# 08_power.net
KiCad netlist of a schematic drawn in Altium Designer
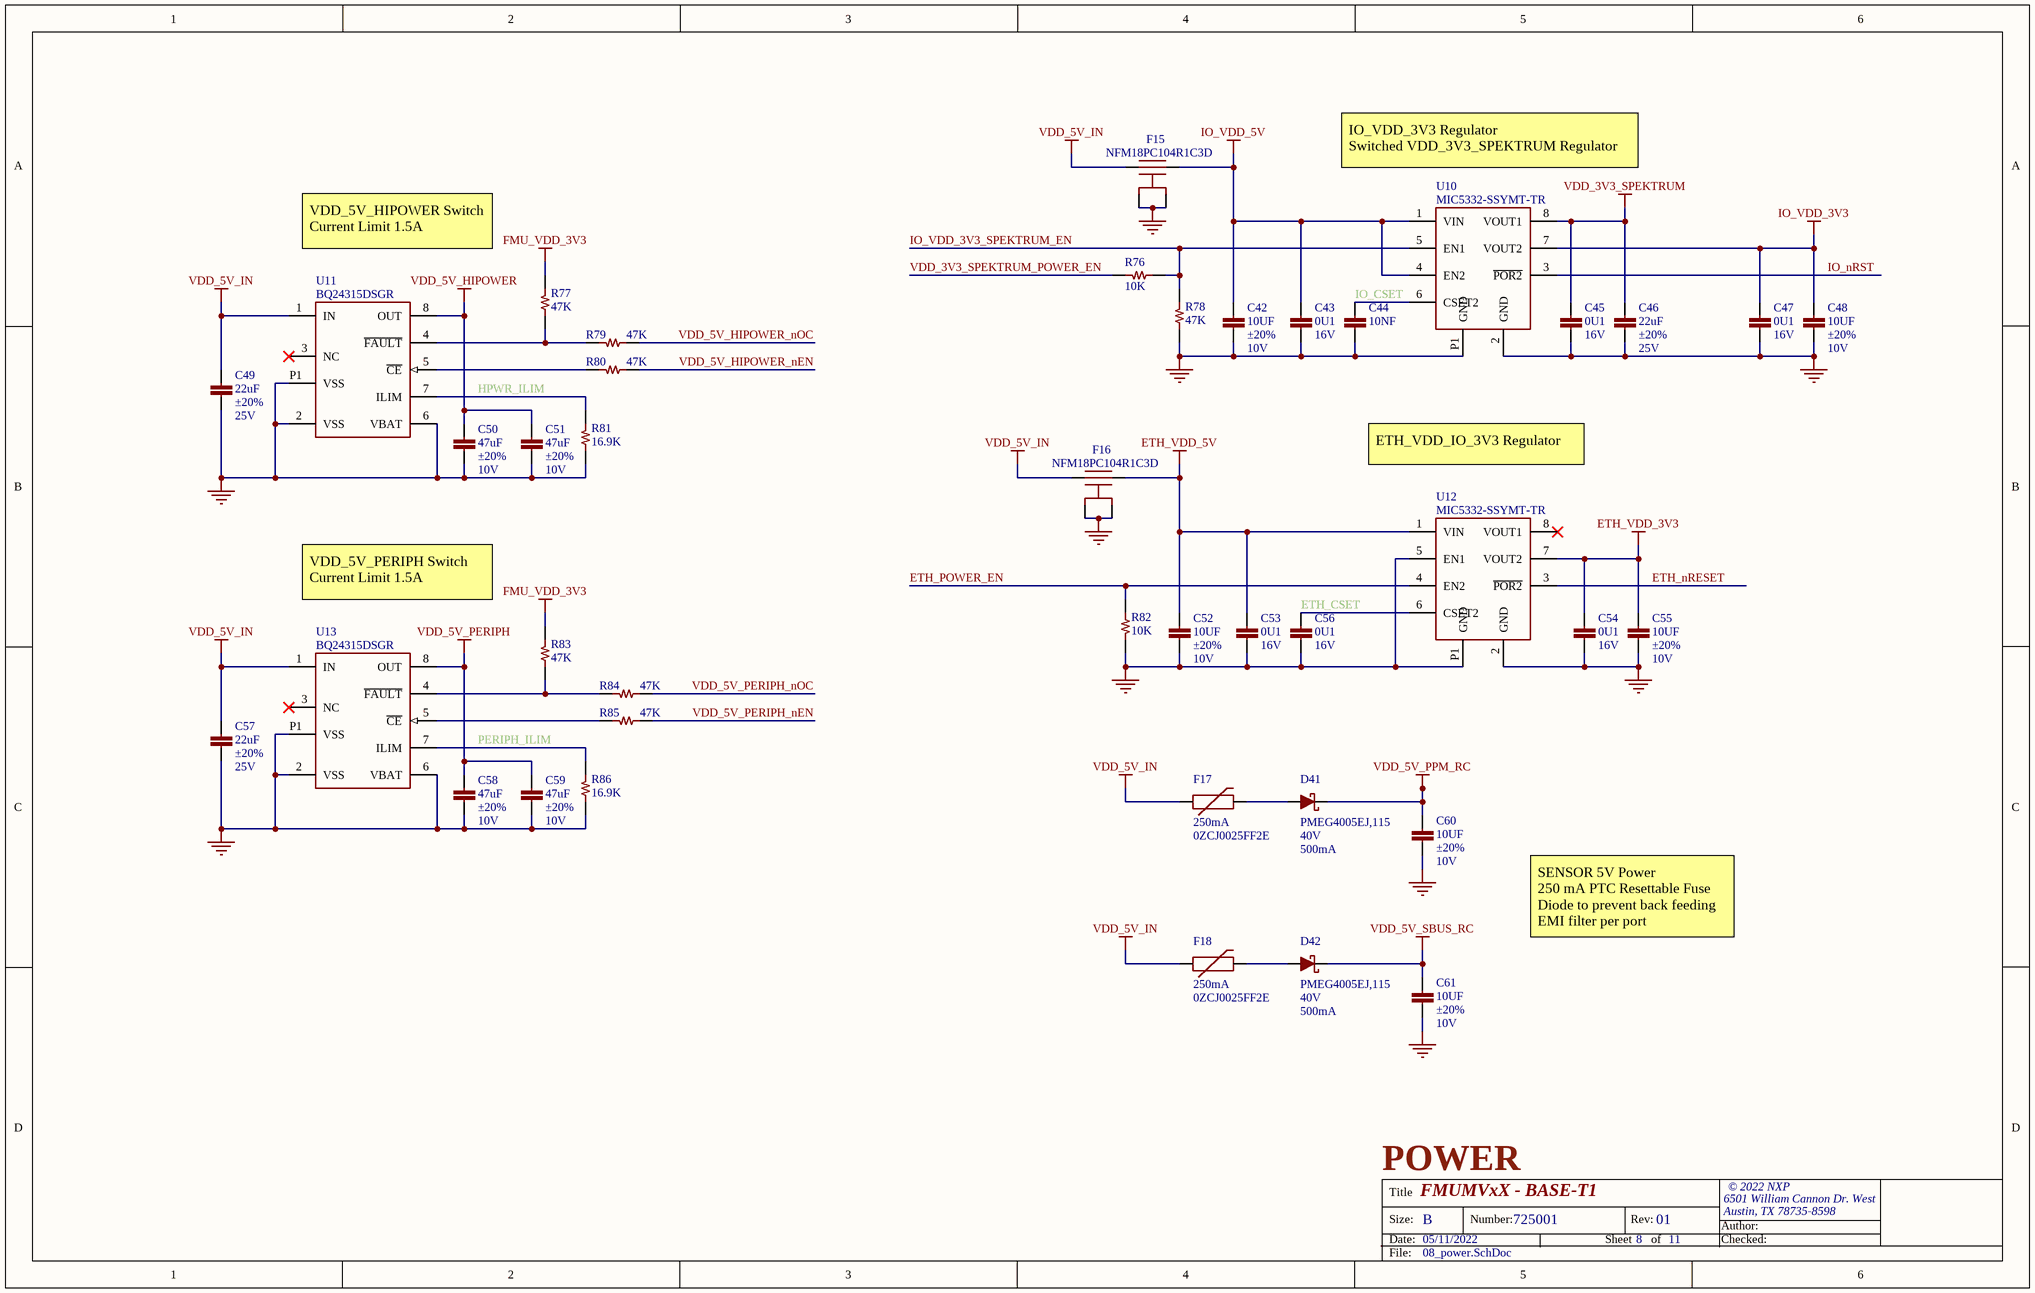
[diagram p0: 08_power.SchDoc]

(export (version "E")
  (design (tool "Eeschema 10.0.6"))
  (components
    (comp (ref "C42")
      (value "10UF")
      (footprint "CAPC100X50X56L25N")
      (description "CAP CER 10UF 20% 10V X5R 0402")
      (fields
        (field (name "MANUFACTURER") "Samsung Electro-Mechanics")
        (field (name "MANUFACTURER PART NUMBER") "CL05A106MP5NUNC")
        (field (name "TOLERANCE") "±20%")
        (field (name "VOLTAGE - RATED") "10V")
      )
      (libsource (lib "NscDG_Integrated_Library") (part "CAP_10UF_20%_10V_X5R_0402"))
    )
    (comp (ref "C43")
      (value "0U1")
      (footprint "CAPC100X50X56L25N")
      (description "CAP CER 0.1UF 10% 16V X7R 0402")
      (fields
        (field (name "TOLERANCE") "±10%")
        (field (name "MANUFACTURER") "Murata Electronics")
        (field (name "VOLTAGE - RATED") "16V")
      )
      (libsource (lib "NscDG_Integrated_Library") (part "CAP_0U1_16V_X7R_0402"))
    )
    (comp (ref "C44")
      (value "10NF")
      (footprint "CAPC100X50X56L25N")
      (description "CAP CER 10NF 10% 50V X7R 0402")
      (fields
        (field (name "TOLERANCE") "±10%")
        (field (name "MANUFACTURER") "Murata Electronics North America")
      )
      (libsource (lib "NscDG_Integrated_Library") (part "CAP_10NF_10%_50V_X7R_0402"))
    )
    (comp (ref "C45")
      (value "0U1")
      (footprint "CAPC100X50X56L25N")
      (description "CAP CER 0.1UF 10% 16V X7R 0402")
      (fields
        (field (name "TOLERANCE") "±10%")
        (field (name "MANUFACTURER") "Murata Electronics")
        (field (name "VOLTAGE - RATED") "16V")
      )
      (libsource (lib "NscDG_Integrated_Library") (part "CAP_0U1_16V_X7R_0402"))
    )
    (comp (ref "C46")
      (value "22uF")
      (footprint "CAPC200X125X70L40N")
      (description "CAP CER 22UF 20% 25V X5R 0805")
      (fields
        (field (name "MANUFACTURER") "Murata Electronics")
        (field (name "MANUFACTURER PART NUMBER") "GRT21BR61E226ME13L")
        (field (name "TOLERANCE") "±20%")
        (field (name "VOLTAGE - RATED") "25V")
      )
      (libsource (lib "NscDG_Integrated_Library") (part "CAP_22UF_20%_25V_X5R_0805"))
    )
    (comp (ref "C47")
      (value "0U1")
      (footprint "CAPC100X50X56L25N")
      (description "CAP CER 0.1UF 10% 16V X7R 0402")
      (fields
        (field (name "TOLERANCE") "±10%")
        (field (name "MANUFACTURER") "Murata Electronics")
        (field (name "VOLTAGE - RATED") "16V")
      )
      (libsource (lib "NscDG_Integrated_Library") (part "CAP_0U1_16V_X7R_0402"))
    )
    (comp (ref "C48")
      (value "10UF")
      (footprint "CAPC100X50X56L25N")
      (description "CAP CER 10UF 20% 10V X5R 0402")
      (fields
        (field (name "MANUFACTURER") "Samsung Electro-Mechanics")
        (field (name "MANUFACTURER PART NUMBER") "CL05A106MP5NUNC")
        (field (name "TOLERANCE") "±20%")
        (field (name "VOLTAGE - RATED") "10V")
      )
      (libsource (lib "NscDG_Integrated_Library") (part "CAP_10UF_20%_10V_X5R_0402"))
    )
    (comp (ref "C49")
      (value "22uF")
      (footprint "CAPC200X125X70L40N")
      (description "CAP CER 22UF 20% 25V X5R 0805")
      (fields
        (field (name "MANUFACTURER") "Murata Electronics")
        (field (name "MANUFACTURER PART NUMBER") "GRT21BR61E226ME13L")
        (field (name "TOLERANCE") "±20%")
        (field (name "VOLTAGE - RATED") "25V")
      )
      (libsource (lib "NscDG_Integrated_Library") (part "CAP_22UF_20%_25V_X5R_0805"))
    )
    (comp (ref "C50")
      (value "47uF")
      (footprint "CAPC200X125X145L45N")
      (description "CAP CER 47UF 20% 10V X5R 0805")
      (fields
        (field (name "MANUFACTURER") "Murata Electronics North America")
        (field (name "MANUFACTURER PART NUMBER") "GRM21BR61A476ME15L")
        (field (name "TOLERANCE") "±20%")
        (field (name "VOLTAGE - RATED") "10V")
      )
      (libsource (lib "NscDG_Integrated_Library") (part "CAP_47UF_20%_10V_X5R_0805"))
    )
    (comp (ref "C51")
      (value "47uF")
      (footprint "CAPC200X125X145L45N")
      (description "CAP CER 47UF 20% 10V X5R 0805")
      (fields
        (field (name "MANUFACTURER") "Murata Electronics North America")
        (field (name "MANUFACTURER PART NUMBER") "GRM21BR61A476ME15L")
        (field (name "TOLERANCE") "±20%")
        (field (name "VOLTAGE - RATED") "10V")
      )
      (libsource (lib "NscDG_Integrated_Library") (part "CAP_47UF_20%_10V_X5R_0805"))
    )
    (comp (ref "C52")
      (value "10UF")
      (footprint "CAPC100X50X56L25N")
      (description "CAP CER 10UF 20% 10V X5R 0402")
      (fields
        (field (name "MANUFACTURER") "Samsung Electro-Mechanics")
        (field (name "MANUFACTURER PART NUMBER") "CL05A106MP5NUNC")
        (field (name "TOLERANCE") "±20%")
        (field (name "VOLTAGE - RATED") "10V")
      )
      (libsource (lib "NscDG_Integrated_Library") (part "CAP_10UF_20%_10V_X5R_0402"))
    )
    (comp (ref "C53")
      (value "0U1")
      (footprint "CAPC100X50X56L25N")
      (description "CAP CER 0.1UF 10% 16V X7R 0402")
      (fields
        (field (name "TOLERANCE") "±10%")
        (field (name "MANUFACTURER") "Murata Electronics")
        (field (name "VOLTAGE - RATED") "16V")
      )
      (libsource (lib "NscDG_Integrated_Library") (part "CAP_0U1_16V_X7R_0402"))
    )
    (comp (ref "C54")
      (value "0U1")
      (footprint "CAPC100X50X56L25N")
      (description "CAP CER 0.1UF 10% 16V X7R 0402")
      (fields
        (field (name "TOLERANCE") "±10%")
        (field (name "MANUFACTURER") "Murata Electronics")
        (field (name "VOLTAGE - RATED") "16V")
      )
      (libsource (lib "NscDG_Integrated_Library") (part "CAP_0U1_16V_X7R_0402"))
    )
    (comp (ref "C55")
      (value "10UF")
      (footprint "CAPC100X50X56L25N")
      (description "CAP CER 10UF 20% 10V X5R 0402")
      (fields
        (field (name "MANUFACTURER") "Samsung Electro-Mechanics")
        (field (name "MANUFACTURER PART NUMBER") "CL05A106MP5NUNC")
        (field (name "TOLERANCE") "±20%")
        (field (name "VOLTAGE - RATED") "10V")
      )
      (libsource (lib "NscDG_Integrated_Library") (part "CAP_10UF_20%_10V_X5R_0402"))
    )
    (comp (ref "C56")
      (value "0U1")
      (footprint "CAPC100X50X56L25N")
      (description "CAP CER 0.1UF 10% 16V X7R 0402")
      (fields
        (field (name "TOLERANCE") "±10%")
        (field (name "MANUFACTURER") "Murata Electronics")
        (field (name "VOLTAGE - RATED") "16V")
      )
      (libsource (lib "NscDG_Integrated_Library") (part "CAP_0U1_16V_X7R_0402"))
    )
    (comp (ref "C57")
      (value "22uF")
      (footprint "CAPC200X125X70L40N")
      (description "CAP CER 22UF 20% 25V X5R 0805")
      (fields
        (field (name "MANUFACTURER") "Murata Electronics")
        (field (name "MANUFACTURER PART NUMBER") "GRT21BR61E226ME13L")
        (field (name "TOLERANCE") "±20%")
        (field (name "VOLTAGE - RATED") "25V")
      )
      (libsource (lib "NscDG_Integrated_Library") (part "CAP_22UF_20%_25V_X5R_0805"))
    )
    (comp (ref "C58")
      (value "47uF")
      (footprint "CAPC200X125X145L45N")
      (description "CAP CER 47UF 20% 10V X5R 0805")
      (fields
        (field (name "MANUFACTURER") "Murata Electronics North America")
        (field (name "MANUFACTURER PART NUMBER") "GRM21BR61A476ME15L")
        (field (name "TOLERANCE") "±20%")
        (field (name "VOLTAGE - RATED") "10V")
      )
      (libsource (lib "NscDG_Integrated_Library") (part "CAP_47UF_20%_10V_X5R_0805"))
    )
    (comp (ref "C59")
      (value "47uF")
      (footprint "CAPC200X125X145L45N")
      (description "CAP CER 47UF 20% 10V X5R 0805")
      (fields
        (field (name "MANUFACTURER") "Murata Electronics North America")
        (field (name "MANUFACTURER PART NUMBER") "GRM21BR61A476ME15L")
        (field (name "TOLERANCE") "±20%")
        (field (name "VOLTAGE - RATED") "10V")
      )
      (libsource (lib "NscDG_Integrated_Library") (part "CAP_47UF_20%_10V_X5R_0805"))
    )
    (comp (ref "C60")
      (value "10UF")
      (footprint "CAPC100X50X56L25N")
      (description "CAP CER 10UF 20% 10V X5R 0402")
      (fields
        (field (name "MANUFACTURER") "Samsung Electro-Mechanics")
        (field (name "MANUFACTURER PART NUMBER") "CL05A106MP5NUNC")
        (field (name "TOLERANCE") "±20%")
        (field (name "VOLTAGE - RATED") "10V")
      )
      (libsource (lib "NscDG_Integrated_Library") (part "CAP_10UF_20%_10V_X5R_0402"))
    )
    (comp (ref "C61")
      (value "10UF")
      (footprint "CAPC100X50X56L25N")
      (description "CAP CER 10UF 20% 10V X5R 0402")
      (fields
        (field (name "MANUFACTURER") "Samsung Electro-Mechanics")
        (field (name "MANUFACTURER PART NUMBER") "CL05A106MP5NUNC")
        (field (name "TOLERANCE") "±20%")
        (field (name "VOLTAGE - RATED") "10V")
      )
      (libsource (lib "NscDG_Integrated_Library") (part "CAP_10UF_20%_10V_X5R_0402"))
    )
    (comp (ref "D41")
      (value "DIODE SCHOTTKY 40V 500MA SOD323F")
      (footprint "SODFL2512X80L40X35N")
      (fields
        (field (name "MANUFACTURER") "Nexperia USA Inc.")
        (field (name "MANUFACTURER PART NUMBER") "PMEG4005EJ,115")
        (field (name "VOLTAGE") "40V")
        (field (name "CURRENT") "500mA")
      )
      (libsource (lib "NscDG_Integrated_Library") (part "DIODE_SCHOTTKY_LOW_VF_40V_500MA_SOD323F"))
    )
    (comp (ref "D42")
      (value "DIODE SCHOTTKY 40V 500MA SOD323F")
      (footprint "SODFL2512X80L40X35N")
      (fields
        (field (name "MANUFACTURER") "Nexperia USA Inc.")
        (field (name "MANUFACTURER PART NUMBER") "PMEG4005EJ,115")
        (field (name "VOLTAGE") "40V")
        (field (name "CURRENT") "500mA")
      )
      (libsource (lib "NscDG_Integrated_Library") (part "DIODE_SCHOTTKY_LOW_VF_40V_500MA_SOD323F"))
    )
    (comp (ref "F15")
      (value "FILTER CAP FEEDTHRU 0.1UF 20% 16V 0603")
      (footprint "NFM18PC104R1C3_0603_NO_VIA")
      (fields
        (field (name "TOLERANCE") "±20%")
        (field (name "MANUFACTURER") "Murata Electronics North America")
        (field (name "MANUFACTURER PART NUMBER") "NFM18PC104R1C3D")
      )
      (libsource (lib "NscDG_Integrated_Library") (part "FILTER_0.1uF_16V_2A_NO_VIA_0603"))
    )
    (comp (ref "F16")
      (value "FILTER CAP FEEDTHRU 0.1UF 20% 16V 0603")
      (footprint "NFM18PC104R1C3_0603_NO_VIA")
      (fields
        (field (name "TOLERANCE") "±20%")
        (field (name "MANUFACTURER") "Murata Electronics North America")
        (field (name "MANUFACTURER PART NUMBER") "NFM18PC104R1C3D")
      )
      (libsource (lib "NscDG_Integrated_Library") (part "FILTER_0.1uF_16V_2A_NO_VIA_0603"))
    )
    (comp (ref "F17")
      (value "FUSE PTC RESETTABLE 250MA 16V 1206")
      (footprint "PTC-1206")
      (fields
        (field (name "MANUFACTURER") "Bel Fuse Inc.")
        (field (name "CURRENT HOLD") "250mA")
        (field (name "MANUFACTURER PART NUMBER") "0ZCJ0025FF2E")
      )
      (libsource (lib "NscDG_Integrated_Library") (part "FUSE_PTC_250MA_SMD"))
    )
    (comp (ref "F18")
      (value "FUSE PTC RESETTABLE 250MA 16V 1206")
      (footprint "PTC-1206")
      (fields
        (field (name "MANUFACTURER") "Bel Fuse Inc.")
        (field (name "CURRENT HOLD") "250mA")
        (field (name "MANUFACTURER PART NUMBER") "0ZCJ0025FF2E")
      )
      (libsource (lib "NscDG_Integrated_Library") (part "FUSE_PTC_250MA_SMD"))
    )
    (comp (ref "R76")
      (value "10K")
      (footprint "RESC100X50X40L25")
      (description "RES SMD 10K OHM 1% 1/16W 0402")
      (fields (field (name "TOLERANCE") "±1%") (field (name "MANUFACTURER") "Vishay Dale"))
      (libsource (lib "NscDG_Integrated_Library") (part "RES_10K_1%_1/16W_0402"))
    )
    (comp (ref "R77")
      (value "47K")
      (footprint "RESC100X50X40L25")
      (description "RES SMD 47K OHM 1% 1/16W 0402")
      (fields (field (name "TOLERANCE") "±1%") (field (name "MANUFACTURER") "Yageo"))
      (libsource (lib "NscDG_Integrated_Library") (part "RES_47K_1%_1/16W_0402"))
    )
    (comp (ref "R78")
      (value "47K")
      (footprint "RESC100X50X40L25")
      (description "RES SMD 47K OHM 1% 1/16W 0402")
      (fields (field (name "TOLERANCE") "±1%") (field (name "MANUFACTURER") "Yageo"))
      (libsource (lib "NscDG_Integrated_Library") (part "RES_47K_1%_1/16W_0402"))
    )
    (comp (ref "R79")
      (value "47K")
      (footprint "RESC100X50X40L25")
      (description "RES SMD 47K OHM 1% 1/16W 0402")
      (fields (field (name "TOLERANCE") "±1%") (field (name "MANUFACTURER") "Yageo"))
      (libsource (lib "NscDG_Integrated_Library") (part "RES_47K_1%_1/16W_0402"))
    )
    (comp (ref "R80")
      (value "47K")
      (footprint "RESC100X50X40L25")
      (description "RES SMD 47K OHM 1% 1/16W 0402")
      (fields (field (name "TOLERANCE") "±1%") (field (name "MANUFACTURER") "Yageo"))
      (libsource (lib "NscDG_Integrated_Library") (part "RES_47K_1%_1/16W_0402"))
    )
    (comp (ref "R81")
      (value "16.9K")
      (footprint "RESC100X50X40L25")
      (description "RES SMD 16.9K OHM 1% 1/16W 0402")
      (fields (field (name "TOLERANCE") "±1%") (field (name "MANUFACTURER") "Yageo"))
      (libsource (lib "NscDG_Integrated_Library") (part "RES_16.9K_1%_1/16W_0402"))
    )
    (comp (ref "R82")
      (value "10K")
      (footprint "RESC100X50X40L25")
      (description "RES SMD 10K OHM 1% 1/16W 0402")
      (fields (field (name "TOLERANCE") "±1%") (field (name "MANUFACTURER") "Vishay Dale"))
      (libsource (lib "NscDG_Integrated_Library") (part "RES_10K_1%_1/16W_0402"))
    )
    (comp (ref "R83")
      (value "47K")
      (footprint "RESC100X50X40L25")
      (description "RES SMD 47K OHM 1% 1/16W 0402")
      (fields (field (name "TOLERANCE") "±1%") (field (name "MANUFACTURER") "Yageo"))
      (libsource (lib "NscDG_Integrated_Library") (part "RES_47K_1%_1/16W_0402"))
    )
    (comp (ref "R84")
      (value "47K")
      (footprint "RESC100X50X40L25")
      (description "RES SMD 47K OHM 1% 1/16W 0402")
      (fields (field (name "TOLERANCE") "±1%") (field (name "MANUFACTURER") "Yageo"))
      (libsource (lib "NscDG_Integrated_Library") (part "RES_47K_1%_1/16W_0402"))
    )
    (comp (ref "R85")
      (value "47K")
      (footprint "RESC100X50X40L25")
      (description "RES SMD 47K OHM 1% 1/16W 0402")
      (fields (field (name "TOLERANCE") "±1%") (field (name "MANUFACTURER") "Yageo"))
      (libsource (lib "NscDG_Integrated_Library") (part "RES_47K_1%_1/16W_0402"))
    )
    (comp (ref "R86")
      (value "16.9K")
      (footprint "RESC100X50X40L25")
      (description "RES SMD 16.9K OHM 1% 1/16W 0402")
      (fields (field (name "TOLERANCE") "±1%") (field (name "MANUFACTURER") "Yageo"))
      (libsource (lib "NscDG_Integrated_Library") (part "RES_16.9K_1%_1/16W_0402"))
    )
    (comp (ref "U10")
      (value "IC REG LIN 3.3V/3.3V 8TMLF")
      (footprint "My_Integrated_Library:SON9P50_200X200X60L35X25T120X60N")
      (fields
        (field (name "MANUFACTURER") "Microchip Technology")
        (field (name "MANUFACTURER PART NUMBER") "MIC5332-SSYMT-TR")
      )
      (libsource (lib "NscDG_Integrated_Library") (part "IC_MIC5332-SSYMT-TR"))
    )
    (comp (ref "U11")
      (value "IC LI+ CHARGER FRONT END 8SON")
      (footprint "SON9P50_200X200X80L30X25T160X80N")
      (fields
        (field (name "MANUFACTURER") "Texas Instruments")
        (field (name "MANUFACTURER PART NUMBER") "BQ24315DSGR")
      )
      (libsource (lib "NscDG_Integrated_Library") (part "IC_BQ24315DSGT_8WSON"))
    )
    (comp (ref "U12")
      (value "IC REG LIN 3.3V/3.3V 8TMLF")
      (footprint "My_Integrated_Library:SON9P50_200X200X60L35X25T120X60N")
      (fields
        (field (name "MANUFACTURER") "Microchip Technology")
        (field (name "MANUFACTURER PART NUMBER") "MIC5332-SSYMT-TR")
      )
      (libsource (lib "NscDG_Integrated_Library") (part "IC_MIC5332-SSYMT-TR"))
    )
    (comp (ref "U13")
      (value "IC LI+ CHARGER FRONT END 8SON")
      (footprint "SON9P50_200X200X80L30X25T160X80N")
      (fields
        (field (name "MANUFACTURER") "Texas Instruments")
        (field (name "MANUFACTURER PART NUMBER") "BQ24315DSGR")
      )
      (libsource (lib "NscDG_Integrated_Library") (part "IC_BQ24315DSGT_8WSON"))
    )
  )
  (nets
    (net (code "1") (name "/ETH_CSET") (class "Default")
      (node (ref "C56") (pin "1") (pinfunction "1_1") (pintype "passive"))
      (node (ref "U12") (pin "6") (pinfunction "CSET2_6") (pintype "passive"))
    )
    (net (code "2") (name "/ETH_POWER_EN") (class "Default")
      (node (ref "R82") (pin "2") (pinfunction "2_2") (pintype "passive"))
      (node (ref "U12") (pin "4") (pinfunction "EN2_4") (pintype "passive"))
    )
    (net (code "3") (name "/ETH_nRESET") (class "Default")
      (node (ref "U12") (pin "3") (pinfunction "~{POR2}_3") (pintype "passive"))
    )
    (net (code "4") (name "/HPWR_ILIM") (class "Default")
      (node (ref "R81") (pin "1") (pinfunction "1_1") (pintype "passive"))
      (node (ref "U11") (pin "7") (pinfunction "ILIM_7") (pintype "passive"))
    )
    (net (code "5") (name "/IO_CSET") (class "Default")
      (node (ref "C44") (pin "1") (pinfunction "1_1") (pintype "passive"))
      (node (ref "U10") (pin "6") (pinfunction "CSET2_6") (pintype "passive"))
    )
    (net (code "6") (name "/IO_VDD_3V3_SPEKTRUM_EN") (class "Default")
      (node (ref "R76") (pin "2") (pinfunction "2_2") (pintype "passive"))
      (node (ref "R78") (pin "1") (pinfunction "1_1") (pintype "passive"))
      (node (ref "U10") (pin "5") (pinfunction "EN1_5") (pintype "passive"))
    )
    (net (code "7") (name "/IO_nRST") (class "Default")
      (node (ref "U10") (pin "3") (pinfunction "~{POR2}_3") (pintype "passive"))
    )
    (net (code "8") (name "/PERIPH_ILIM") (class "Default")
      (node (ref "R86") (pin "1") (pinfunction "1_1") (pintype "passive"))
      (node (ref "U13") (pin "7") (pinfunction "ILIM_7") (pintype "passive"))
    )
    (net (code "9") (name "/VDD_3V3_SPEKTRUM_POWER_EN") (class "Default")
      (node (ref "R76") (pin "1") (pinfunction "1_1") (pintype "passive"))
    )
    (net (code "10") (name "/VDD_5V_HIPOWER_nEN") (class "Default")
      (node (ref "R80") (pin "2") (pinfunction "2_2") (pintype "passive"))
    )
    (net (code "11") (name "/VDD_5V_HIPOWER_nOC") (class "Default")
      (node (ref "R79") (pin "2") (pinfunction "2_2") (pintype "passive"))
    )
    (net (code "12") (name "/VDD_5V_PERIPH_nEN") (class "Default")
      (node (ref "R85") (pin "2") (pinfunction "2_2") (pintype "passive"))
    )
    (net (code "13") (name "/VDD_5V_PERIPH_nOC") (class "Default")
      (node (ref "R84") (pin "2") (pinfunction "2_2") (pintype "passive"))
    )
    (net (code "14") (name "ETH_VDD_3V3") (class "Default")
      (node (ref "C54") (pin "1") (pinfunction "1_1") (pintype "passive"))
      (node (ref "C55") (pin "1") (pinfunction "1_1") (pintype "passive"))
      (node (ref "U12") (pin "7") (pinfunction "VOUT2_7") (pintype "passive"))
    )
    (net (code "15") (name "ETH_VDD_5V") (class "Default")
      (node (ref "C52") (pin "1") (pinfunction "1_1") (pintype "passive"))
      (node (ref "C53") (pin "1") (pinfunction "1_1") (pintype "passive"))
      (node (ref "F16") (pin "3") (pinfunction "3_3") (pintype "passive"))
      (node (ref "U12") (pin "1") (pinfunction "VIN_1") (pintype "power_in"))
    )
    (net (code "16") (name "FMU_VDD_3V3") (class "Default")
      (node (ref "R77") (pin "1") (pinfunction "1_1") (pintype "passive"))
      (node (ref "R83") (pin "1") (pinfunction "1_1") (pintype "passive"))
    )
    (net (code "17") (name "GND") (class "Default")
      (node (ref "C42") (pin "2") (pinfunction "2_2") (pintype "passive"))
      (node (ref "C43") (pin "2") (pinfunction "2_2") (pintype "passive"))
      (node (ref "C44") (pin "2") (pinfunction "2_2") (pintype "passive"))
      (node (ref "C45") (pin "2") (pinfunction "2_2") (pintype "passive"))
      (node (ref "C46") (pin "2") (pinfunction "2_2") (pintype "passive"))
      (node (ref "C47") (pin "2") (pinfunction "2_2") (pintype "passive"))
      (node (ref "C48") (pin "2") (pinfunction "2_2") (pintype "passive"))
      (node (ref "C49") (pin "2") (pinfunction "2_2") (pintype "passive"))
      (node (ref "C50") (pin "2") (pinfunction "2_2") (pintype "passive"))
      (node (ref "C51") (pin "2") (pinfunction "2_2") (pintype "passive"))
      (node (ref "C52") (pin "2") (pinfunction "2_2") (pintype "passive"))
      (node (ref "C53") (pin "2") (pinfunction "2_2") (pintype "passive"))
      (node (ref "C54") (pin "2") (pinfunction "2_2") (pintype "passive"))
      (node (ref "C55") (pin "2") (pinfunction "2_2") (pintype "passive"))
      (node (ref "C56") (pin "2") (pinfunction "2_2") (pintype "passive"))
      (node (ref "C57") (pin "2") (pinfunction "2_2") (pintype "passive"))
      (node (ref "C58") (pin "2") (pinfunction "2_2") (pintype "passive"))
      (node (ref "C59") (pin "2") (pinfunction "2_2") (pintype "passive"))
      (node (ref "C60") (pin "2") (pinfunction "2_2") (pintype "passive"))
      (node (ref "C61") (pin "2") (pinfunction "2_2") (pintype "passive"))
      (node (ref "F15") (pin "2A") (pinfunction "GND_2A") (pintype "passive"))
      (node (ref "F15") (pin "2B") (pinfunction "GND_2B") (pintype "passive"))
      (node (ref "F16") (pin "2A") (pinfunction "GND_2A") (pintype "passive"))
      (node (ref "F16") (pin "2B") (pinfunction "GND_2B") (pintype "passive"))
      (node (ref "R78") (pin "2") (pinfunction "2_2") (pintype "passive"))
      (node (ref "R81") (pin "2") (pinfunction "2_2") (pintype "passive"))
      (node (ref "R82") (pin "1") (pinfunction "1_1") (pintype "passive"))
      (node (ref "R86") (pin "2") (pinfunction "2_2") (pintype "passive"))
      (node (ref "U10") (pin "2") (pinfunction "GND_2") (pintype "passive"))
      (node (ref "U10") (pin "P1") (pinfunction "GND_P1") (pintype "passive"))
      (node (ref "U11") (pin "2") (pinfunction "VSS_2") (pintype "passive"))
      (node (ref "U11") (pin "6") (pinfunction "VBAT_6") (pintype "passive"))
      (node (ref "U11") (pin "P1") (pinfunction "VSS_P1") (pintype "passive"))
      (node (ref "U12") (pin "2") (pinfunction "GND_2") (pintype "passive"))
      (node (ref "U12") (pin "5") (pinfunction "EN1_5") (pintype "passive"))
      (node (ref "U12") (pin "P1") (pinfunction "GND_P1") (pintype "passive"))
      (node (ref "U13") (pin "2") (pinfunction "VSS_2") (pintype "passive"))
      (node (ref "U13") (pin "6") (pinfunction "VBAT_6") (pintype "passive"))
      (node (ref "U13") (pin "P1") (pinfunction "VSS_P1") (pintype "passive"))
    )
    (net (code "18") (name "IO_VDD_3V3") (class "Default")
      (node (ref "C47") (pin "1") (pinfunction "1_1") (pintype "passive"))
      (node (ref "C48") (pin "1") (pinfunction "1_1") (pintype "passive"))
      (node (ref "U10") (pin "7") (pinfunction "VOUT2_7") (pintype "passive"))
    )
    (net (code "19") (name "IO_VDD_5V") (class "Default")
      (node (ref "C42") (pin "1") (pinfunction "1_1") (pintype "passive"))
      (node (ref "C43") (pin "1") (pinfunction "1_1") (pintype "passive"))
      (node (ref "F15") (pin "3") (pinfunction "3_3") (pintype "passive"))
      (node (ref "U10") (pin "1") (pinfunction "VIN_1") (pintype "power_in"))
      (node (ref "U10") (pin "4") (pinfunction "EN2_4") (pintype "passive"))
    )
    (net (code "20") (name "Net-(D41-PadA)") (class "Default")
      (node (ref "D41") (pin "A") (pinfunction "A_A") (pintype "passive"))
      (node (ref "F17") (pin "2") (pinfunction "2_2") (pintype "passive"))
    )
    (net (code "21") (name "Net-(D42-PadA)") (class "Default")
      (node (ref "D42") (pin "A") (pinfunction "A_A") (pintype "passive"))
      (node (ref "F18") (pin "2") (pinfunction "2_2") (pintype "passive"))
    )
    (net (code "22") (name "Net-(U11-~{CE})") (class "Default")
      (node (ref "R80") (pin "1") (pinfunction "1_1") (pintype "passive"))
      (node (ref "U11") (pin "5") (pinfunction "~{CE}_5") (pintype "input"))
    )
    (net (code "23") (name "Net-(U11-~{FAULT})") (class "Default")
      (node (ref "R77") (pin "2") (pinfunction "2_2") (pintype "passive"))
      (node (ref "R79") (pin "1") (pinfunction "1_1") (pintype "passive"))
      (node (ref "U11") (pin "4") (pinfunction "~{FAULT}_4") (pintype "open_collector"))
    )
    (net (code "24") (name "Net-(U13-~{CE})") (class "Default")
      (node (ref "R85") (pin "1") (pinfunction "1_1") (pintype "passive"))
      (node (ref "U13") (pin "5") (pinfunction "~{CE}_5") (pintype "input"))
    )
    (net (code "25") (name "Net-(U13-~{FAULT})") (class "Default")
      (node (ref "R83") (pin "2") (pinfunction "2_2") (pintype "passive"))
      (node (ref "R84") (pin "1") (pinfunction "1_1") (pintype "passive"))
      (node (ref "U13") (pin "4") (pinfunction "~{FAULT}_4") (pintype "open_collector"))
    )
    (net (code "26") (name "VDD_3V3_SPEKTRUM") (class "Default")
      (node (ref "C45") (pin "1") (pinfunction "1_1") (pintype "passive"))
      (node (ref "C46") (pin "1") (pinfunction "1_1") (pintype "passive"))
      (node (ref "U10") (pin "8") (pinfunction "VOUT1_8") (pintype "passive"))
    )
    (net (code "27") (name "VDD_5V_HIPOWER") (class "Default")
      (node (ref "C50") (pin "1") (pinfunction "1_1") (pintype "passive"))
      (node (ref "C51") (pin "1") (pinfunction "1_1") (pintype "passive"))
      (node (ref "U11") (pin "8") (pinfunction "OUT_8") (pintype "passive"))
    )
    (net (code "28") (name "VDD_5V_IN") (class "Default")
      (node (ref "C49") (pin "1") (pinfunction "1_1") (pintype "passive"))
      (node (ref "C57") (pin "1") (pinfunction "1_1") (pintype "passive"))
      (node (ref "F15") (pin "1") (pinfunction "1_1") (pintype "passive"))
      (node (ref "F16") (pin "1") (pinfunction "1_1") (pintype "passive"))
      (node (ref "F17") (pin "1") (pinfunction "1_1") (pintype "passive"))
      (node (ref "F18") (pin "1") (pinfunction "1_1") (pintype "passive"))
      (node (ref "U11") (pin "1") (pinfunction "IN_1") (pintype "passive"))
      (node (ref "U13") (pin "1") (pinfunction "IN_1") (pintype "passive"))
    )
    (net (code "29") (name "VDD_5V_PERIPH") (class "Default")
      (node (ref "C58") (pin "1") (pinfunction "1_1") (pintype "passive"))
      (node (ref "C59") (pin "1") (pinfunction "1_1") (pintype "passive"))
      (node (ref "U13") (pin "8") (pinfunction "OUT_8") (pintype "passive"))
    )
    (net (code "30") (name "VDD_5V_PPM_RC") (class "Default")
      (node (ref "C60") (pin "1") (pinfunction "1_1") (pintype "passive"))
      (node (ref "D41") (pin "C") (pinfunction "C_C") (pintype "passive"))
    )
    (net (code "31") (name "VDD_5V_SBUS_RC") (class "Default")
      (node (ref "C61") (pin "1") (pinfunction "1_1") (pintype "passive"))
      (node (ref "D42") (pin "C") (pinfunction "C_C") (pintype "passive"))
    )
    (net (code "32") (name "unconnected-(U11-NC-Pad3)") (class "Default")
      (node (ref "U11") (pin "3") (pinfunction "NC_3") (pintype "passive+no_connect"))
    )
    (net (code "33") (name "unconnected-(U12-VOUT1-Pad8)") (class "Default")
      (node (ref "U12") (pin "8") (pinfunction "VOUT1_8") (pintype "passive+no_connect"))
    )
    (net (code "34") (name "unconnected-(U13-NC-Pad3)") (class "Default")
      (node (ref "U13") (pin "3") (pinfunction "NC_3") (pintype "passive+no_connect"))
    )
  )
)
